# eth_ksz8567r_switch.net
KiCad netlist of a schematic drawn in Altium Designer
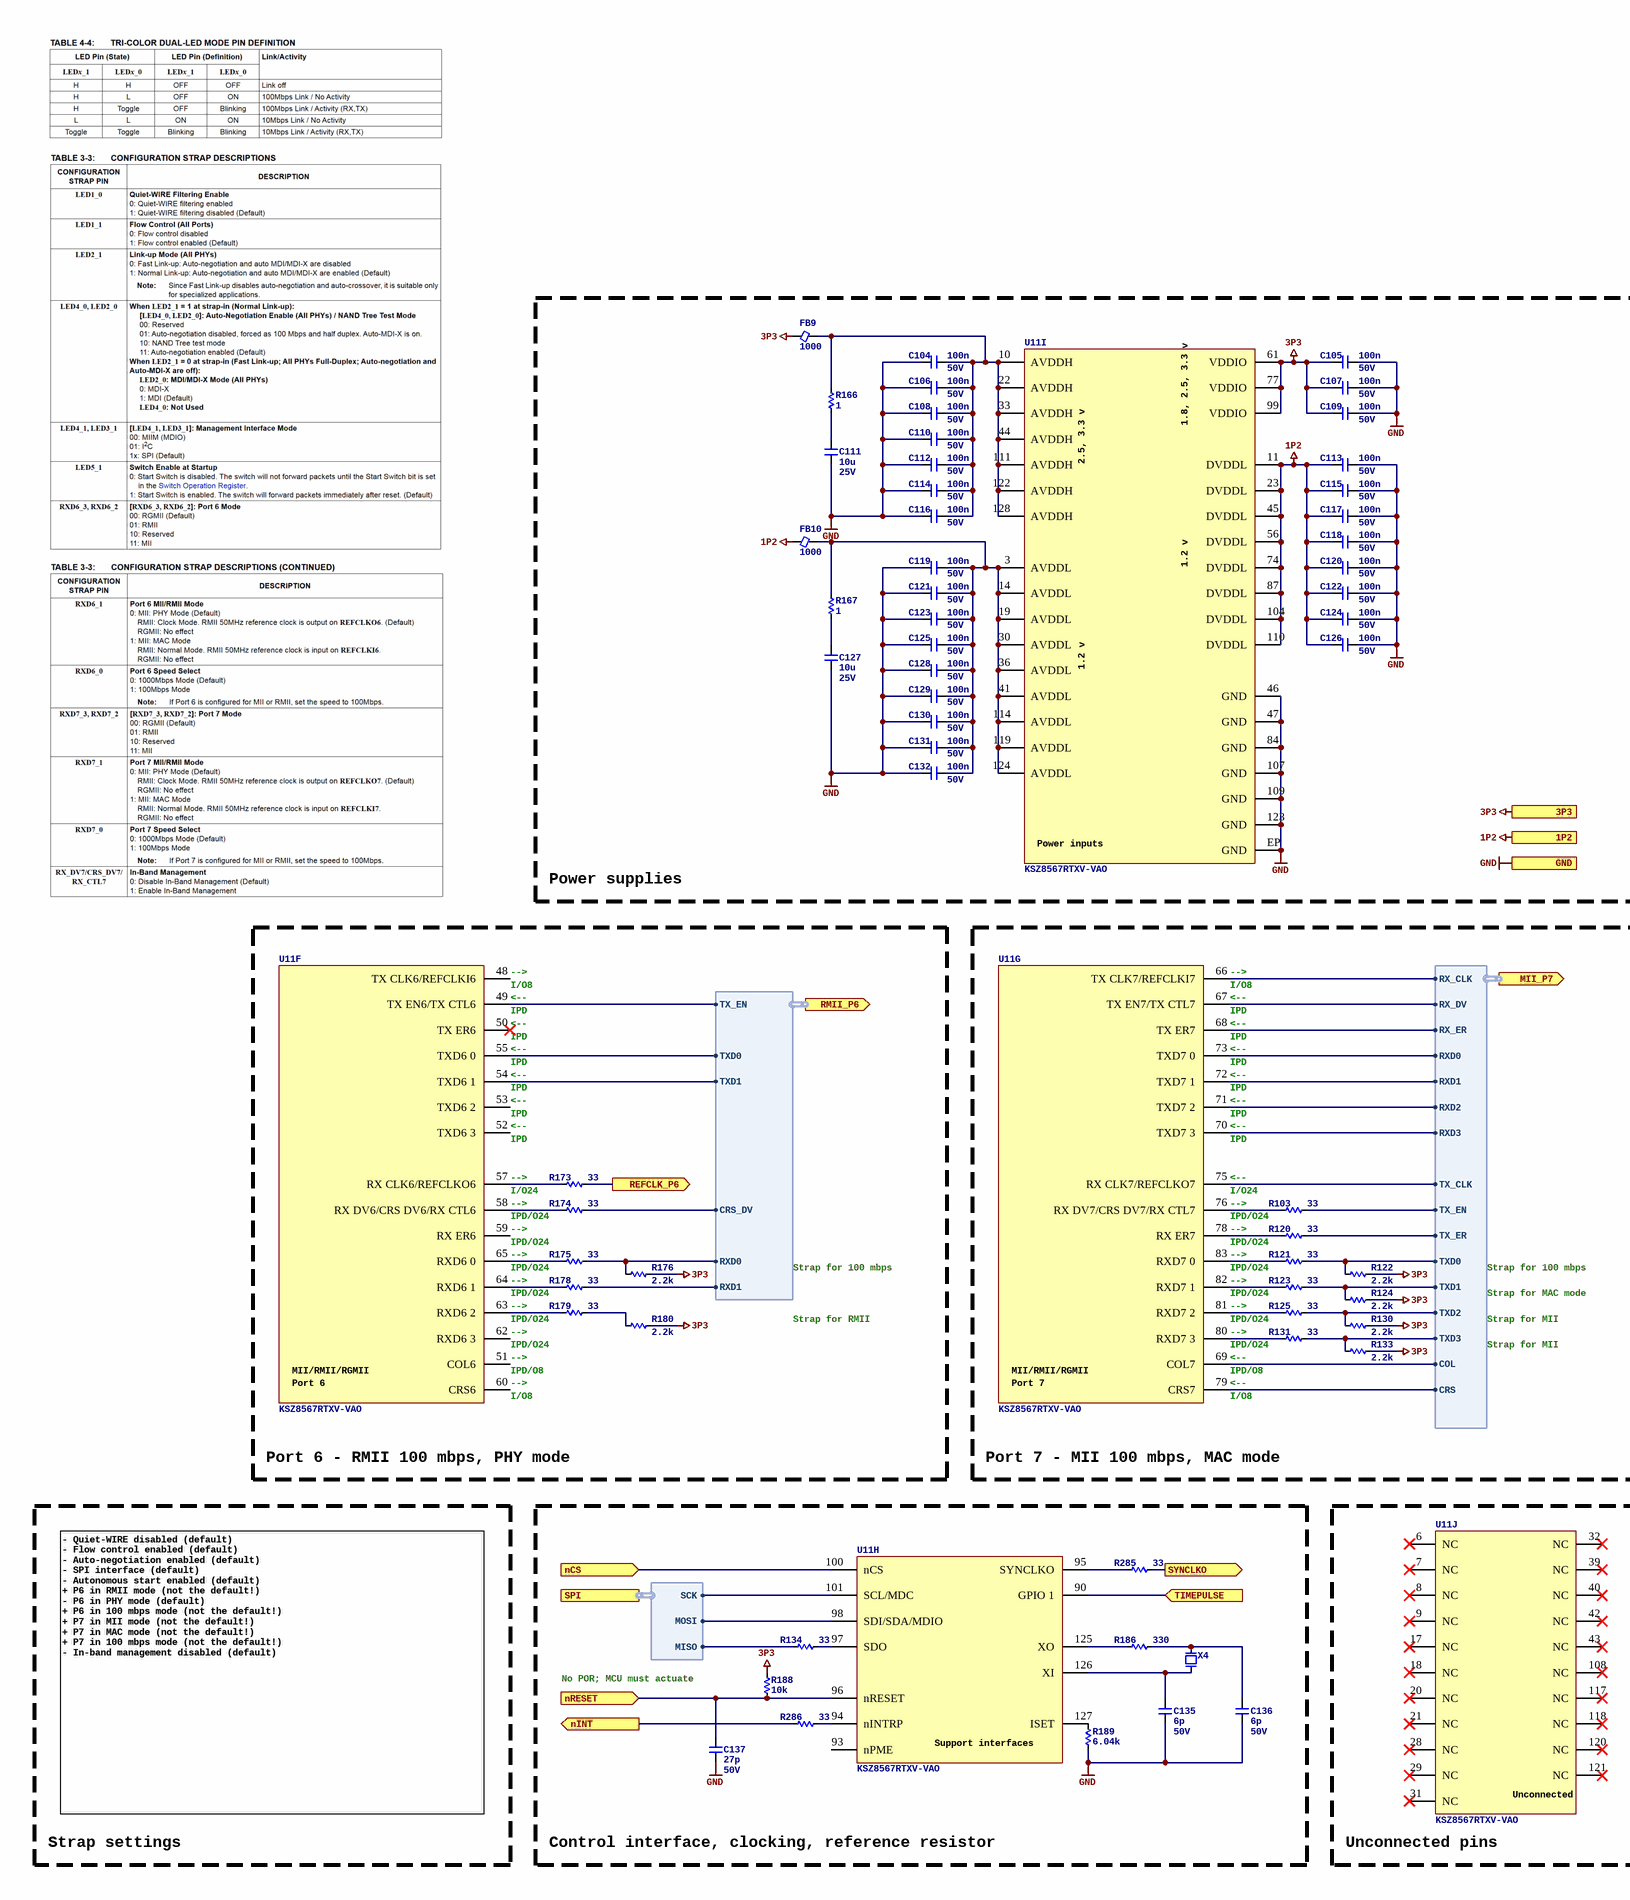
[diagram p0: eth_ksz8567r_switch.SchDoc, left]
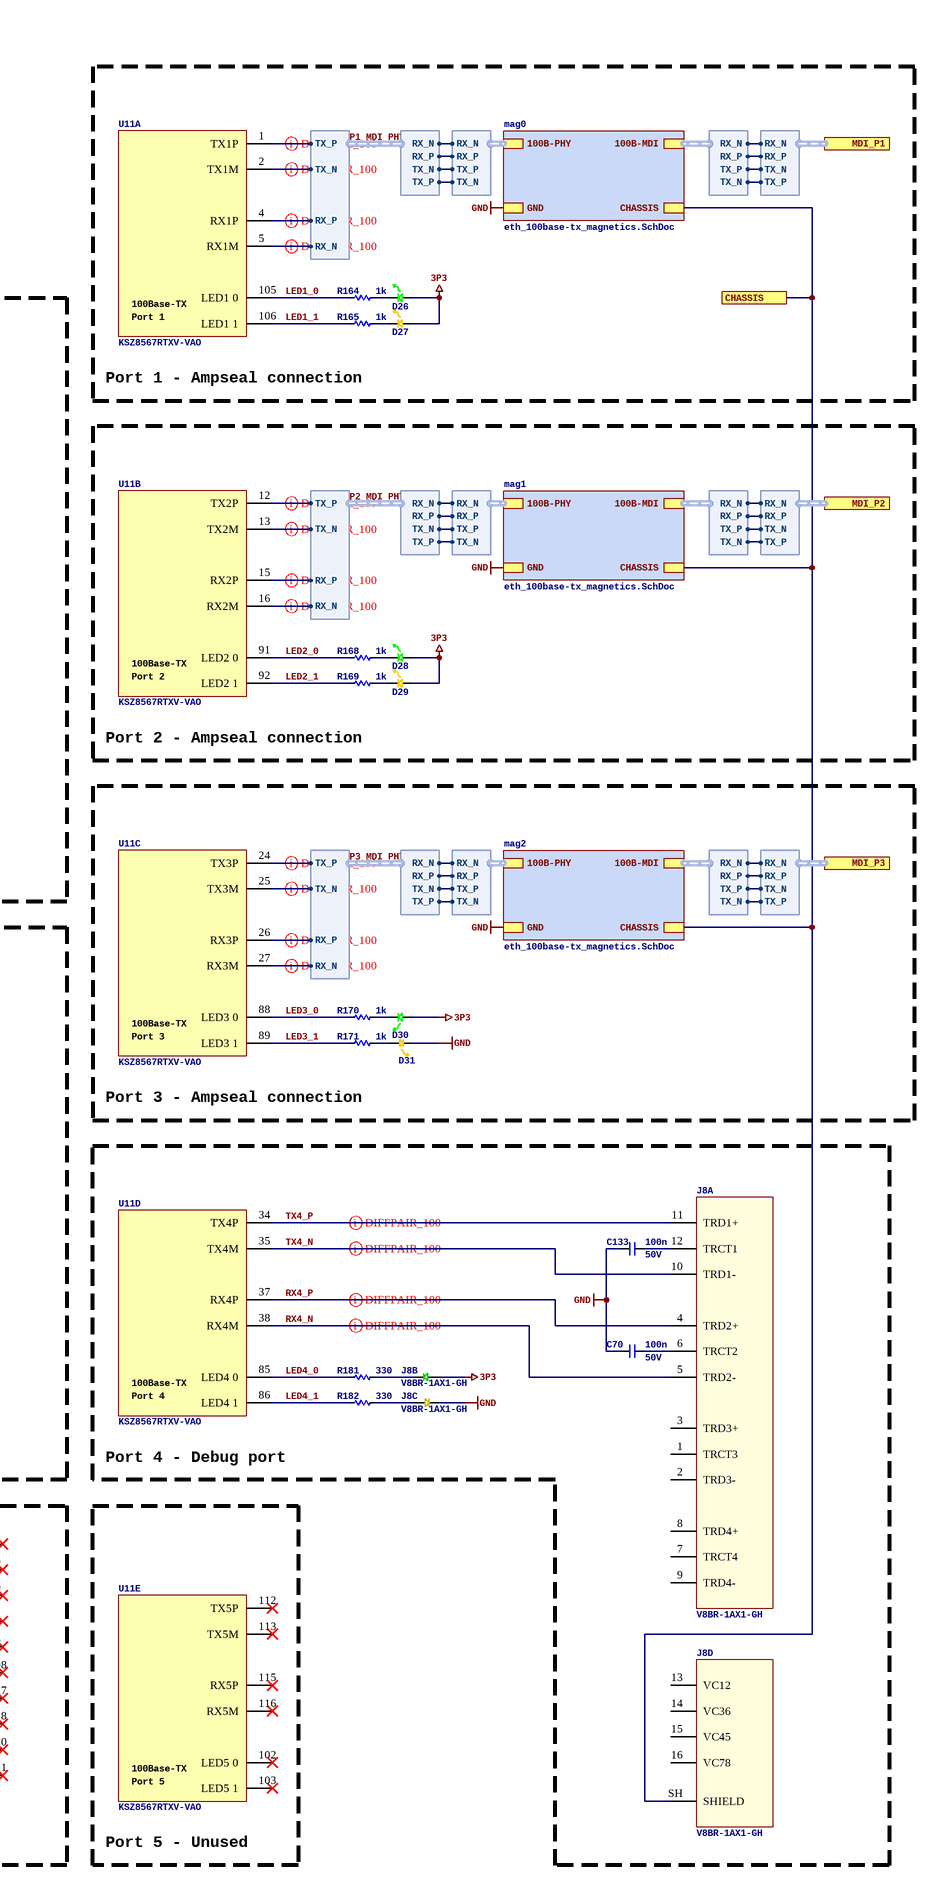
[diagram p1: eth_ksz8567r_switch.SchDoc, right]

(export (version "E")
  (design (tool "Eeschema 10.0.6"))
  (components
    (comp (ref "C70")
      (value "CL05B104KB54PNC")
      (footprint "C0402")
      (fields
        (field (name "CAPACITANCE") "100n")
        (field (name "MANUFACTURER") "Samsung Electro-Mechanics")
        (field (name "VOLTAGE RATING") "50V")
      )
      (libsource (lib "database") (part "__template_cap"))
    )
    (comp (ref "C104")
      (value "CL05B104KB54PNC")
      (footprint "C0402")
      (fields
        (field (name "CAPACITANCE") "100n")
        (field (name "MANUFACTURER") "Samsung Electro-Mechanics")
        (field (name "VOLTAGE RATING") "50V")
      )
      (libsource (lib "database") (part "__template_cap"))
    )
    (comp (ref "C105")
      (value "CL05B104KB54PNC")
      (footprint "C0402")
      (fields
        (field (name "CAPACITANCE") "100n")
        (field (name "MANUFACTURER") "Samsung Electro-Mechanics")
        (field (name "VOLTAGE RATING") "50V")
      )
      (libsource (lib "database") (part "__template_cap"))
    )
    (comp (ref "C106")
      (value "CL05B104KB54PNC")
      (footprint "C0402")
      (fields
        (field (name "CAPACITANCE") "100n")
        (field (name "MANUFACTURER") "Samsung Electro-Mechanics")
        (field (name "VOLTAGE RATING") "50V")
      )
      (libsource (lib "database") (part "__template_cap"))
    )
    (comp (ref "C107")
      (value "CL05B104KB54PNC")
      (footprint "C0402")
      (fields
        (field (name "CAPACITANCE") "100n")
        (field (name "MANUFACTURER") "Samsung Electro-Mechanics")
        (field (name "VOLTAGE RATING") "50V")
      )
      (libsource (lib "database") (part "__template_cap"))
    )
    (comp (ref "C108")
      (value "CL05B104KB54PNC")
      (footprint "C0402")
      (fields
        (field (name "CAPACITANCE") "100n")
        (field (name "MANUFACTURER") "Samsung Electro-Mechanics")
        (field (name "VOLTAGE RATING") "50V")
      )
      (libsource (lib "database") (part "__template_cap"))
    )
    (comp (ref "C109")
      (value "CL05B104KB54PNC")
      (footprint "C0402")
      (fields
        (field (name "CAPACITANCE") "100n")
        (field (name "MANUFACTURER") "Samsung Electro-Mechanics")
        (field (name "VOLTAGE RATING") "50V")
      )
      (libsource (lib "database") (part "__template_cap"))
    )
    (comp (ref "C110")
      (value "CL05B104KB54PNC")
      (footprint "C0402")
      (fields
        (field (name "CAPACITANCE") "100n")
        (field (name "MANUFACTURER") "Samsung Electro-Mechanics")
        (field (name "VOLTAGE RATING") "50V")
      )
      (libsource (lib "database") (part "__template_cap"))
    )
    (comp (ref "C111")
      (value "CL21B106KAYQNNE")
      (footprint "C0805")
      (fields
        (field (name "CAPACITANCE") "10u")
        (field (name "MANUFACTURER") "Samsung Electro-Mechanics")
        (field (name "VOLTAGE RATING") "25V")
      )
      (libsource (lib "database") (part "__template_cap"))
    )
    (comp (ref "C112")
      (value "CL05B104KB54PNC")
      (footprint "C0402")
      (fields
        (field (name "CAPACITANCE") "100n")
        (field (name "MANUFACTURER") "Samsung Electro-Mechanics")
        (field (name "VOLTAGE RATING") "50V")
      )
      (libsource (lib "database") (part "__template_cap"))
    )
    (comp (ref "C113")
      (value "CL05B104KB54PNC")
      (footprint "C0402")
      (fields
        (field (name "CAPACITANCE") "100n")
        (field (name "MANUFACTURER") "Samsung Electro-Mechanics")
        (field (name "VOLTAGE RATING") "50V")
      )
      (libsource (lib "database") (part "__template_cap"))
    )
    (comp (ref "C114")
      (value "CL05B104KB54PNC")
      (footprint "C0402")
      (fields
        (field (name "CAPACITANCE") "100n")
        (field (name "MANUFACTURER") "Samsung Electro-Mechanics")
        (field (name "VOLTAGE RATING") "50V")
      )
      (libsource (lib "database") (part "__template_cap"))
    )
    (comp (ref "C115")
      (value "CL05B104KB54PNC")
      (footprint "C0402")
      (fields
        (field (name "CAPACITANCE") "100n")
        (field (name "MANUFACTURER") "Samsung Electro-Mechanics")
        (field (name "VOLTAGE RATING") "50V")
      )
      (libsource (lib "database") (part "__template_cap"))
    )
    (comp (ref "C116")
      (value "CL05B104KB54PNC")
      (footprint "C0402")
      (fields
        (field (name "CAPACITANCE") "100n")
        (field (name "MANUFACTURER") "Samsung Electro-Mechanics")
        (field (name "VOLTAGE RATING") "50V")
      )
      (libsource (lib "database") (part "__template_cap"))
    )
    (comp (ref "C117")
      (value "CL05B104KB54PNC")
      (footprint "C0402")
      (fields
        (field (name "CAPACITANCE") "100n")
        (field (name "MANUFACTURER") "Samsung Electro-Mechanics")
        (field (name "VOLTAGE RATING") "50V")
      )
      (libsource (lib "database") (part "__template_cap"))
    )
    (comp (ref "C118")
      (value "CL05B104KB54PNC")
      (footprint "C0402")
      (fields
        (field (name "CAPACITANCE") "100n")
        (field (name "MANUFACTURER") "Samsung Electro-Mechanics")
        (field (name "VOLTAGE RATING") "50V")
      )
      (libsource (lib "database") (part "__template_cap"))
    )
    (comp (ref "C119")
      (value "CL05B104KB54PNC")
      (footprint "C0402")
      (fields
        (field (name "CAPACITANCE") "100n")
        (field (name "MANUFACTURER") "Samsung Electro-Mechanics")
        (field (name "VOLTAGE RATING") "50V")
      )
      (libsource (lib "database") (part "__template_cap"))
    )
    (comp (ref "C120")
      (value "CL05B104KB54PNC")
      (footprint "C0402")
      (fields
        (field (name "CAPACITANCE") "100n")
        (field (name "MANUFACTURER") "Samsung Electro-Mechanics")
        (field (name "VOLTAGE RATING") "50V")
      )
      (libsource (lib "database") (part "__template_cap"))
    )
    (comp (ref "C121")
      (value "CL05B104KB54PNC")
      (footprint "C0402")
      (fields
        (field (name "CAPACITANCE") "100n")
        (field (name "MANUFACTURER") "Samsung Electro-Mechanics")
        (field (name "VOLTAGE RATING") "50V")
      )
      (libsource (lib "database") (part "__template_cap"))
    )
    (comp (ref "C122")
      (value "CL05B104KB54PNC")
      (footprint "C0402")
      (fields
        (field (name "CAPACITANCE") "100n")
        (field (name "MANUFACTURER") "Samsung Electro-Mechanics")
        (field (name "VOLTAGE RATING") "50V")
      )
      (libsource (lib "database") (part "__template_cap"))
    )
    (comp (ref "C123")
      (value "CL05B104KB54PNC")
      (footprint "C0402")
      (fields
        (field (name "CAPACITANCE") "100n")
        (field (name "MANUFACTURER") "Samsung Electro-Mechanics")
        (field (name "VOLTAGE RATING") "50V")
      )
      (libsource (lib "database") (part "__template_cap"))
    )
    (comp (ref "C124")
      (value "CL05B104KB54PNC")
      (footprint "C0402")
      (fields
        (field (name "CAPACITANCE") "100n")
        (field (name "MANUFACTURER") "Samsung Electro-Mechanics")
        (field (name "VOLTAGE RATING") "50V")
      )
      (libsource (lib "database") (part "__template_cap"))
    )
    (comp (ref "C125")
      (value "CL05B104KB54PNC")
      (footprint "C0402")
      (fields
        (field (name "CAPACITANCE") "100n")
        (field (name "MANUFACTURER") "Samsung Electro-Mechanics")
        (field (name "VOLTAGE RATING") "50V")
      )
      (libsource (lib "database") (part "__template_cap"))
    )
    (comp (ref "C126")
      (value "CL05B104KB54PNC")
      (footprint "C0402")
      (fields
        (field (name "CAPACITANCE") "100n")
        (field (name "MANUFACTURER") "Samsung Electro-Mechanics")
        (field (name "VOLTAGE RATING") "50V")
      )
      (libsource (lib "database") (part "__template_cap"))
    )
    (comp (ref "C127")
      (value "CL21B106KAYQNNE")
      (footprint "C0805")
      (fields
        (field (name "CAPACITANCE") "10u")
        (field (name "MANUFACTURER") "Samsung Electro-Mechanics")
        (field (name "VOLTAGE RATING") "25V")
      )
      (libsource (lib "database") (part "__template_cap"))
    )
    (comp (ref "C128")
      (value "CL05B104KB54PNC")
      (footprint "C0402")
      (fields
        (field (name "CAPACITANCE") "100n")
        (field (name "MANUFACTURER") "Samsung Electro-Mechanics")
        (field (name "VOLTAGE RATING") "50V")
      )
      (libsource (lib "database") (part "__template_cap"))
    )
    (comp (ref "C129")
      (value "CL05B104KB54PNC")
      (footprint "C0402")
      (fields
        (field (name "CAPACITANCE") "100n")
        (field (name "MANUFACTURER") "Samsung Electro-Mechanics")
        (field (name "VOLTAGE RATING") "50V")
      )
      (libsource (lib "database") (part "__template_cap"))
    )
    (comp (ref "C130")
      (value "CL05B104KB54PNC")
      (footprint "C0402")
      (fields
        (field (name "CAPACITANCE") "100n")
        (field (name "MANUFACTURER") "Samsung Electro-Mechanics")
        (field (name "VOLTAGE RATING") "50V")
      )
      (libsource (lib "database") (part "__template_cap"))
    )
    (comp (ref "C131")
      (value "CL05B104KB54PNC")
      (footprint "C0402")
      (fields
        (field (name "CAPACITANCE") "100n")
        (field (name "MANUFACTURER") "Samsung Electro-Mechanics")
        (field (name "VOLTAGE RATING") "50V")
      )
      (libsource (lib "database") (part "__template_cap"))
    )
    (comp (ref "C132")
      (value "CL05B104KB54PNC")
      (footprint "C0402")
      (fields
        (field (name "CAPACITANCE") "100n")
        (field (name "MANUFACTURER") "Samsung Electro-Mechanics")
        (field (name "VOLTAGE RATING") "50V")
      )
      (libsource (lib "database") (part "__template_cap"))
    )
    (comp (ref "C133")
      (value "CL05B104KB54PNC")
      (footprint "C0402")
      (fields
        (field (name "CAPACITANCE") "100n")
        (field (name "MANUFACTURER") "Samsung Electro-Mechanics")
        (field (name "VOLTAGE RATING") "50V")
      )
      (libsource (lib "database") (part "__template_cap"))
    )
    (comp (ref "C135")
      (value "0402CG6R0C500NT")
      (footprint "C0402")
      (fields
        (field (name "CAPACITANCE") "6p")
        (field (name "MANUFACTURER") "FH(Guangdong Fenghua Advanced Tech)")
        (field (name "VOLTAGE RATING") "50V")
      )
      (libsource (lib "database") (part "__template_cap"))
    )
    (comp (ref "C136")
      (value "0402CG6R0C500NT")
      (footprint "C0402")
      (fields
        (field (name "CAPACITANCE") "6p")
        (field (name "MANUFACTURER") "FH(Guangdong Fenghua Advanced Tech)")
        (field (name "VOLTAGE RATING") "50V")
      )
      (libsource (lib "database") (part "__template_cap"))
    )
    (comp (ref "C137")
      (value "0402CG270J500NT")
      (footprint "C0402")
      (fields
        (field (name "CAPACITANCE") "27p")
        (field (name "MANUFACTURER") "FH(Guangdong Fenghua Advanced Tech)")
        (field (name "VOLTAGE RATING") "50V")
      )
      (libsource (lib "database") (part "__template_cap"))
    )
    (comp (ref "D26")
      (value "LTST-C190GKT")
      (footprint "LED_0603P_GREEN")
      (description "LED GREEN CLEAR 0603 SMD")
      (fields (field (name "MANUFACTURER") "Lite-On Inc"))
      (libsource (lib "SSCP") (part "LED_0603_GREEN_LTST-C190GKT"))
    )
    (comp (ref "D27")
      (value "LTST-C190AKT")
      (footprint "LED_0603P_AMBER")
      (description "LED AMBER CLEAR 0603 SMD")
      (fields (field (name "MANUFACTURER") "Lite-On Inc"))
      (libsource (lib "SSCP") (part "LED_0603_AMBER_LTST-C190AKT"))
    )
    (comp (ref "D28")
      (value "LTST-C190GKT")
      (footprint "LED_0603P_GREEN")
      (description "LED GREEN CLEAR 0603 SMD")
      (fields (field (name "MANUFACTURER") "Lite-On Inc"))
      (libsource (lib "SSCP") (part "LED_0603_GREEN_LTST-C190GKT"))
    )
    (comp (ref "D29")
      (value "LTST-C190AKT")
      (footprint "LED_0603P_AMBER")
      (description "LED AMBER CLEAR 0603 SMD")
      (fields (field (name "MANUFACTURER") "Lite-On Inc"))
      (libsource (lib "SSCP") (part "LED_0603_AMBER_LTST-C190AKT"))
    )
    (comp (ref "D30")
      (value "LTST-C190GKT")
      (footprint "LED_0603P_GREEN")
      (description "LED GREEN CLEAR 0603 SMD")
      (fields (field (name "MANUFACTURER") "Lite-On Inc"))
      (libsource (lib "") (part "LED_0603_GREEN_LTST-C190GKT_1"))
    )
    (comp (ref "D31")
      (value "LTST-C190AKT")
      (footprint "LED_0603P_AMBER")
      (description "LED AMBER CLEAR 0603 SMD")
      (fields (field (name "MANUFACTURER") "Lite-On Inc"))
      (libsource (lib "SSCP") (part "LED_0603_AMBER_LTST-C190AKT"))
    )
    (comp (ref "FB9")
      (value "HCB2012KF-102T10")
      (footprint "FB0805")
      (fields (field (name "MANUFACTURER") "TAI-TECH") (field (name "CURRENT RATING (MA)") "1000"))
      (libsource (lib "database") (part "__template_fb"))
    )
    (comp (ref "FB10")
      (value "HCB2012KF-102T10")
      (footprint "FB0805")
      (fields (field (name "MANUFACTURER") "TAI-TECH") (field (name "CURRENT RATING (MA)") "1000"))
      (libsource (lib "database") (part "__template_fb"))
    )
    (comp (ref "J8")
      (value "V8BR-1AX1-GH")
      (footprint "BELFUSE_V8BR-1AX1-GH")
      (description "Conn RJ-45 F 8 POS 1.02mm Solder ST Thru-Hole 20 Terminal 1 Port Tray")
      (fields (field (name "MANUFACTURER") "Bel"))
      (libsource (lib "SSCP") (part "CONN_BELFUSE_ETHERNET_V8BR-1AX1-GH"))
    )
    (comp (ref "R103")
      (value "33")
      (footprint "R0402")
      (fields
        (field (name "TOLERANCE") "1%")
        (field (name "MANUFACTURER PART NUMBER") "0402WGF330JTCE")
        (field (name "MANUFACTURER") "UNI-ROYAL(Uniroyal Elec)")
      )
      (libsource (lib "database") (part "__template_resistor"))
    )
    (comp (ref "R120")
      (value "33")
      (footprint "R0402")
      (fields
        (field (name "TOLERANCE") "1%")
        (field (name "MANUFACTURER PART NUMBER") "0402WGF330JTCE")
        (field (name "MANUFACTURER") "UNI-ROYAL(Uniroyal Elec)")
      )
      (libsource (lib "database") (part "__template_resistor"))
    )
    (comp (ref "R121")
      (value "33")
      (footprint "R0402")
      (fields
        (field (name "TOLERANCE") "1%")
        (field (name "MANUFACTURER PART NUMBER") "0402WGF330JTCE")
        (field (name "MANUFACTURER") "UNI-ROYAL(Uniroyal Elec)")
      )
      (libsource (lib "database") (part "__template_resistor"))
    )
    (comp (ref "R122")
      (value "2.2k")
      (footprint "R0402")
      (fields
        (field (name "TOLERANCE") "1%")
        (field (name "MANUFACTURER PART NUMBER") "0402WGF2201TCE")
        (field (name "MANUFACTURER") "UNI-ROYAL(Uniroyal Elec)")
      )
      (libsource (lib "database") (part "__template_resistor"))
    )
    (comp (ref "R123")
      (value "33")
      (footprint "R0402")
      (fields
        (field (name "TOLERANCE") "1%")
        (field (name "MANUFACTURER PART NUMBER") "0402WGF330JTCE")
        (field (name "MANUFACTURER") "UNI-ROYAL(Uniroyal Elec)")
      )
      (libsource (lib "database") (part "__template_resistor"))
    )
    (comp (ref "R124")
      (value "2.2k")
      (footprint "R0402")
      (fields
        (field (name "TOLERANCE") "1%")
        (field (name "MANUFACTURER PART NUMBER") "0402WGF2201TCE")
        (field (name "MANUFACTURER") "UNI-ROYAL(Uniroyal Elec)")
      )
      (libsource (lib "database") (part "__template_resistor"))
    )
    (comp (ref "R125")
      (value "33")
      (footprint "R0402")
      (fields
        (field (name "TOLERANCE") "1%")
        (field (name "MANUFACTURER PART NUMBER") "0402WGF330JTCE")
        (field (name "MANUFACTURER") "UNI-ROYAL(Uniroyal Elec)")
      )
      (libsource (lib "database") (part "__template_resistor"))
    )
    (comp (ref "R130")
      (value "2.2k")
      (footprint "R0402")
      (fields
        (field (name "TOLERANCE") "1%")
        (field (name "MANUFACTURER PART NUMBER") "0402WGF2201TCE")
        (field (name "MANUFACTURER") "UNI-ROYAL(Uniroyal Elec)")
      )
      (libsource (lib "database") (part "__template_resistor"))
    )
    (comp (ref "R131")
      (value "33")
      (footprint "R0402")
      (fields
        (field (name "TOLERANCE") "1%")
        (field (name "MANUFACTURER PART NUMBER") "0402WGF330JTCE")
        (field (name "MANUFACTURER") "UNI-ROYAL(Uniroyal Elec)")
      )
      (libsource (lib "database") (part "__template_resistor"))
    )
    (comp (ref "R133")
      (value "2.2k")
      (footprint "R0402")
      (fields
        (field (name "TOLERANCE") "1%")
        (field (name "MANUFACTURER PART NUMBER") "0402WGF2201TCE")
        (field (name "MANUFACTURER") "UNI-ROYAL(Uniroyal Elec)")
      )
      (libsource (lib "database") (part "__template_resistor"))
    )
    (comp (ref "R134")
      (value "33")
      (footprint "R0402")
      (fields
        (field (name "TOLERANCE") "1%")
        (field (name "MANUFACTURER PART NUMBER") "0402WGF330JTCE")
        (field (name "MANUFACTURER") "UNI-ROYAL(Uniroyal Elec)")
      )
      (libsource (lib "database") (part "__template_resistor"))
    )
    (comp (ref "R164")
      (value "1k")
      (footprint "R0402")
      (fields
        (field (name "TOLERANCE") "1%")
        (field (name "MANUFACTURER PART NUMBER") "0402WGF1001TCE")
        (field (name "MANUFACTURER") "UNI-ROYAL(Uniroyal Elec)")
      )
      (libsource (lib "database") (part "__template_resistor"))
    )
    (comp (ref "R165")
      (value "1k")
      (footprint "R0402")
      (fields
        (field (name "TOLERANCE") "1%")
        (field (name "MANUFACTURER PART NUMBER") "0402WGF1001TCE")
        (field (name "MANUFACTURER") "UNI-ROYAL(Uniroyal Elec)")
      )
      (libsource (lib "database") (part "__template_resistor"))
    )
    (comp (ref "R166")
      (value "1")
      (footprint "R0402")
      (fields
        (field (name "TOLERANCE") "1%")
        (field (name "MANUFACTURER PART NUMBER") "CRCW04021R00FKED")
        (field (name "MANUFACTURER") "Vishay Intertech")
      )
      (libsource (lib "database") (part "__template_resistor"))
    )
    (comp (ref "R167")
      (value "1")
      (footprint "R0402")
      (fields
        (field (name "TOLERANCE") "1%")
        (field (name "MANUFACTURER PART NUMBER") "CRCW04021R00FKED")
        (field (name "MANUFACTURER") "Vishay Intertech")
      )
      (libsource (lib "database") (part "__template_resistor"))
    )
    (comp (ref "R168")
      (value "1k")
      (footprint "R0402")
      (fields
        (field (name "TOLERANCE") "1%")
        (field (name "MANUFACTURER PART NUMBER") "0402WGF1001TCE")
        (field (name "MANUFACTURER") "UNI-ROYAL(Uniroyal Elec)")
      )
      (libsource (lib "database") (part "__template_resistor"))
    )
    (comp (ref "R169")
      (value "1k")
      (footprint "R0402")
      (fields
        (field (name "TOLERANCE") "1%")
        (field (name "MANUFACTURER PART NUMBER") "0402WGF1001TCE")
        (field (name "MANUFACTURER") "UNI-ROYAL(Uniroyal Elec)")
      )
      (libsource (lib "database") (part "__template_resistor"))
    )
    (comp (ref "R170")
      (value "1k")
      (footprint "R0402")
      (fields
        (field (name "TOLERANCE") "1%")
        (field (name "MANUFACTURER PART NUMBER") "0402WGF1001TCE")
        (field (name "MANUFACTURER") "UNI-ROYAL(Uniroyal Elec)")
      )
      (libsource (lib "database") (part "__template_resistor"))
    )
    (comp (ref "R171")
      (value "1k")
      (footprint "R0402")
      (fields
        (field (name "TOLERANCE") "1%")
        (field (name "MANUFACTURER PART NUMBER") "0402WGF1001TCE")
        (field (name "MANUFACTURER") "UNI-ROYAL(Uniroyal Elec)")
      )
      (libsource (lib "database") (part "__template_resistor"))
    )
    (comp (ref "R173")
      (value "33")
      (footprint "R0402")
      (fields
        (field (name "TOLERANCE") "1%")
        (field (name "MANUFACTURER PART NUMBER") "0402WGF330JTCE")
        (field (name "MANUFACTURER") "UNI-ROYAL(Uniroyal Elec)")
      )
      (libsource (lib "database") (part "__template_resistor"))
    )
    (comp (ref "R174")
      (value "33")
      (footprint "R0402")
      (fields
        (field (name "TOLERANCE") "1%")
        (field (name "MANUFACTURER PART NUMBER") "0402WGF330JTCE")
        (field (name "MANUFACTURER") "UNI-ROYAL(Uniroyal Elec)")
      )
      (libsource (lib "database") (part "__template_resistor"))
    )
    (comp (ref "R175")
      (value "33")
      (footprint "R0402")
      (fields
        (field (name "TOLERANCE") "1%")
        (field (name "MANUFACTURER PART NUMBER") "0402WGF330JTCE")
        (field (name "MANUFACTURER") "UNI-ROYAL(Uniroyal Elec)")
      )
      (libsource (lib "database") (part "__template_resistor"))
    )
    (comp (ref "R176")
      (value "2.2k")
      (footprint "R0402")
      (fields
        (field (name "TOLERANCE") "1%")
        (field (name "MANUFACTURER PART NUMBER") "0402WGF2201TCE")
        (field (name "MANUFACTURER") "UNI-ROYAL(Uniroyal Elec)")
      )
      (libsource (lib "database") (part "__template_resistor"))
    )
    (comp (ref "R178")
      (value "33")
      (footprint "R0402")
      (fields
        (field (name "TOLERANCE") "1%")
        (field (name "MANUFACTURER PART NUMBER") "0402WGF330JTCE")
        (field (name "MANUFACTURER") "UNI-ROYAL(Uniroyal Elec)")
      )
      (libsource (lib "database") (part "__template_resistor"))
    )
    (comp (ref "R179")
      (value "33")
      (footprint "R0402")
      (fields
        (field (name "TOLERANCE") "1%")
        (field (name "MANUFACTURER PART NUMBER") "0402WGF330JTCE")
        (field (name "MANUFACTURER") "UNI-ROYAL(Uniroyal Elec)")
      )
      (libsource (lib "database") (part "__template_resistor"))
    )
    (comp (ref "R180")
      (value "2.2k")
      (footprint "R0402")
      (fields
        (field (name "TOLERANCE") "1%")
        (field (name "MANUFACTURER PART NUMBER") "0402WGF2201TCE")
        (field (name "MANUFACTURER") "UNI-ROYAL(Uniroyal Elec)")
      )
      (libsource (lib "database") (part "__template_resistor"))
    )
    (comp (ref "R181")
      (value "330")
      (footprint "R0402")
      (fields
        (field (name "TOLERANCE") "1%")
        (field (name "MANUFACTURER PART NUMBER") "0402WGF3300TCE")
        (field (name "MANUFACTURER") "UNI-ROYAL(Uniroyal Elec)")
      )
      (libsource (lib "database") (part "__template_resistor"))
    )
    (comp (ref "R182")
      (value "330")
      (footprint "R0402")
      (fields
        (field (name "TOLERANCE") "1%")
        (field (name "MANUFACTURER PART NUMBER") "0402WGF3300TCE")
        (field (name "MANUFACTURER") "UNI-ROYAL(Uniroyal Elec)")
      )
      (libsource (lib "database") (part "__template_resistor"))
    )
    (comp (ref "R186")
      (value "330")
      (footprint "R0402")
      (fields
        (field (name "TOLERANCE") "1%")
        (field (name "MANUFACTURER PART NUMBER") "0402WGF3300TCE")
        (field (name "MANUFACTURER") "UNI-ROYAL(Uniroyal Elec)")
      )
      (libsource (lib "database") (part "__template_resistor"))
    )
    (comp (ref "R188")
      (value "10k")
      (footprint "R0402")
      (fields
        (field (name "TOLERANCE") "1%")
        (field (name "MANUFACTURER PART NUMBER") "0402WGF1002TCE")
        (field (name "MANUFACTURER") "UNI-ROYAL(Uniroyal Elec)")
      )
      (libsource (lib "database") (part "__template_resistor"))
    )
    (comp (ref "R189")
      (value "6.04k")
      (footprint "R0402")
      (fields
        (field (name "TOLERANCE") "1%")
        (field (name "MANUFACTURER PART NUMBER") "0402WGF6041TCE")
        (field (name "MANUFACTURER") "UNI-ROYAL(Uniroyal Elec)")
      )
      (libsource (lib "database") (part "__template_resistor"))
    )
    (comp (ref "R285")
      (value "33")
      (footprint "R0402")
      (fields
        (field (name "TOLERANCE") "1%")
        (field (name "MANUFACTURER PART NUMBER") "0402WGF330JTCE")
        (field (name "MANUFACTURER") "UNI-ROYAL(Uniroyal Elec)")
      )
      (libsource (lib "database") (part "__template_resistor"))
    )
    (comp (ref "R286")
      (value "33")
      (footprint "R0402")
      (fields
        (field (name "TOLERANCE") "1%")
        (field (name "MANUFACTURER PART NUMBER") "0402WGF330JTCE")
        (field (name "MANUFACTURER") "UNI-ROYAL(Uniroyal Elec)")
      )
      (libsource (lib "database") (part "__template_resistor"))
    )
    (comp (ref "U11")
      (value "KSZ8567RTXV-VAO")
      (footprint "MICROCHIP_C04-418B_128TQFP_14X14_10X10EP")
      (description "Automotive Ethernet Switch 7 Port 10Mbps/100Mbps 128-Pin TQFP EP Tray")
      (fields (field (name "MANUFACTURER") "Microchip"))
      (libsource (lib "SSCP") (part "ETH_SWITCH_7PORT_KSZ8567RTXV-VAO"))
    )
    (comp (ref "X4")
      (value "XRCGB25M000F3A00R0")
      (footprint "4_SMD_2.0X1.6MM")
      (description "CRYSTAL 25.000MHZ 6PF SMD")
      (fields (field (name "MANUFACTURER") "Murata"))
      (libsource (lib "SSCP") (part "XTAL_XRCGB25M000F3A00R0"))
    )
  )
  (nets
    (net (code "8") (name "/CHASSIS") (class "Default")
      (node (ref "J8") (pin "SH") (pinfunction "SHIELD_SH") (pintype "passive"))
    )
    (net (code "9") (name "/COL") (class "Default")
      (node (ref "U11") (pin "69") (pinfunction "COL7_69") (pintype "passive"))
    )
    (net (code "10") (name "/CRS") (class "Default")
      (node (ref "U11") (pin "79") (pinfunction "CRS7_79") (pintype "passive"))
    )
    (net (code "11") (name "/CRS_DV") (class "Default") (node (ref "R174") (pin "1") (pintype "passive")))
    (net (code "12") (name "/LED1_0") (class "Default")
      (node (ref "R164") (pin "2") (pintype "passive"))
      (node (ref "U11") (pin "105") (pinfunction "LED1_0_105") (pintype "passive"))
    )
    (net (code "13") (name "/LED1_1") (class "Default")
      (node (ref "R165") (pin "2") (pintype "passive"))
      (node (ref "U11") (pin "106") (pinfunction "LED1_1_106") (pintype "passive"))
    )
    (net (code "14") (name "/LED2_0") (class "Default")
      (node (ref "R168") (pin "2") (pintype "passive"))
      (node (ref "U11") (pin "91") (pinfunction "LED2_0_91") (pintype "passive"))
    )
    (net (code "15") (name "/LED2_1") (class "Default")
      (node (ref "R169") (pin "2") (pintype "passive"))
      (node (ref "U11") (pin "92") (pinfunction "LED2_1_92") (pintype "passive"))
    )
    (net (code "16") (name "/LED3_0") (class "Default")
      (node (ref "R170") (pin "2") (pintype "passive"))
      (node (ref "U11") (pin "88") (pinfunction "LED3_0_88") (pintype "passive"))
    )
    (net (code "17") (name "/LED3_1") (class "Default")
      (node (ref "R171") (pin "2") (pintype "passive"))
      (node (ref "U11") (pin "89") (pinfunction "LED3_1_89") (pintype "passive"))
    )
    (net (code "18") (name "/LED4_0") (class "Default")
      (node (ref "R181") (pin "1") (pintype "passive"))
      (node (ref "U11") (pin "85") (pinfunction "LED4_0_85") (pintype "passive"))
    )
    (net (code "19") (name "/LED4_1") (class "Default")
      (node (ref "R182") (pin "1") (pintype "passive"))
      (node (ref "U11") (pin "86") (pinfunction "LED4_1_86") (pintype "passive"))
    )
    (net (code "20") (name "/MISO") (class "Default") (node (ref "R134") (pin "2") (pintype "passive")))
    (net (code "21") (name "/MOSI") (class "Default")
      (node (ref "U11") (pin "98") (pinfunction "SDI/SDA/MDIO_98") (pintype "passive"))
    )
    (net (code "25") (name "/REFCLK_P6") (class "Default") (node (ref "R173") (pin "1") (pintype "passive")))
    (net (code "26") (name "/RX4_N") (class "Default")
      (node (ref "J8") (pin "5") (pinfunction "TRD2-_5") (pintype "passive"))
      (node (ref "U11") (pin "38") (pinfunction "RX4M_38") (pintype "passive"))
    )
    (net (code "27") (name "/RX4_P") (class "Default")
      (node (ref "J8") (pin "4") (pinfunction "TRD2+_4") (pintype "passive"))
      (node (ref "U11") (pin "37") (pinfunction "RX4P_37") (pintype "passive"))
    )
    (net (code "28") (name "/RXD2") (class "Default")
      (node (ref "U11") (pin "71") (pinfunction "TXD7_2_71") (pintype "passive"))
    )
    (net (code "29") (name "/RXD3") (class "Default")
      (node (ref "U11") (pin "70") (pinfunction "TXD7_3_70") (pintype "passive"))
    )
    (net (code "30") (name "/RX_CLK") (class "Default")
      (node (ref "U11") (pin "66") (pinfunction "TX_CLK7/REFCLKI7_66") (pintype "passive"))
    )
    (net (code "31") (name "/RX_DV") (class "Default")
      (node (ref "U11") (pin "67") (pinfunction "TX_EN7/TX_CTL7_67") (pintype "passive"))
    )
    (net (code "32") (name "/RX_ER") (class "Default")
      (node (ref "U11") (pin "68") (pinfunction "TX_ER7_68") (pintype "passive"))
    )
    (net (code "33") (name "/SCK") (class "Default")
      (node (ref "U11") (pin "101") (pinfunction "SCL/MDC_101") (pintype "passive"))
    )
    (net (code "34") (name "/SYNCLKO") (class "Default") (node (ref "R285") (pin "1") (pintype "passive")))
    (net (code "35") (name "/TIMEPULSE") (class "Default")
      (node (ref "U11") (pin "90") (pinfunction "GPIO_1_90") (pintype "passive"))
    )
    (net (code "36") (name "/TX4_N") (class "Default")
      (node (ref "J8") (pin "10") (pinfunction "TRD1-_10") (pintype "passive"))
      (node (ref "U11") (pin "35") (pinfunction "TX4M_35") (pintype "passive"))
    )
    (net (code "37") (name "/TX4_P") (class "Default")
      (node (ref "J8") (pin "11") (pinfunction "TRD1+_11") (pintype "passive"))
      (node (ref "U11") (pin "34") (pinfunction "TX4P_34") (pintype "passive"))
    )
    (net (code "38") (name "/TXD2") (class "Default")
      (node (ref "R125") (pin "1") (pintype "passive"))
      (node (ref "R130") (pin "2") (pintype "passive"))
    )
    (net (code "39") (name "/TXD3") (class "Default")
      (node (ref "R131") (pin "1") (pintype "passive"))
      (node (ref "R133") (pin "2") (pintype "passive"))
    )
    (net (code "40") (name "/TX_CLK") (class "Default")
      (node (ref "U11") (pin "75") (pinfunction "RX_CLK7/REFCLKO7_75") (pintype "passive"))
    )
    (net (code "41") (name "/TX_ER") (class "Default") (node (ref "R120") (pin "1") (pintype "passive")))
    (net (code "42") (name "/nCS") (class "Default")
      (node (ref "U11") (pin "100") (pinfunction "nCS_100") (pintype "passive"))
    )
    (net (code "43") (name "/nINT") (class "Default") (node (ref "R286") (pin "2") (pintype "passive")))
    (net (code "44") (name "/nRESET") (class "Default")
      (node (ref "C137") (pin "1") (pintype "passive"))
      (node (ref "R188") (pin "2") (pintype "passive"))
      (node (ref "U11") (pin "96") (pinfunction "nRESET_96") (pintype "passive"))
    )
    (net (code "49") (name "1P2") (class "Default")
      (node (ref "C113") (pin "1") (pintype "passive"))
      (node (ref "C115") (pin "1") (pintype "passive"))
      (node (ref "C117") (pin "1") (pintype "passive"))
      (node (ref "C118") (pin "1") (pintype "passive"))
      (node (ref "C120") (pin "1") (pintype "passive"))
      (node (ref "C122") (pin "1") (pintype "passive"))
      (node (ref "C124") (pin "1") (pintype "passive"))
      (node (ref "C126") (pin "1") (pintype "passive"))
      (node (ref "FB10") (pin "1") (pintype "passive"))
      (node (ref "U11") (pin "104") (pinfunction "DVDDL_104") (pintype "passive"))
      (node (ref "U11") (pin "11") (pinfunction "DVDDL_11") (pintype "passive"))
      (node (ref "U11") (pin "110") (pinfunction "DVDDL_110") (pintype "passive"))
      (node (ref "U11") (pin "23") (pinfunction "DVDDL_23") (pintype "passive"))
      (node (ref "U11") (pin "45") (pinfunction "DVDDL_45") (pintype "passive"))
      (node (ref "U11") (pin "56") (pinfunction "DVDDL_56") (pintype "passive"))
      (node (ref "U11") (pin "74") (pinfunction "DVDDL_74") (pintype "passive"))
      (node (ref "U11") (pin "87") (pinfunction "DVDDL_87") (pintype "passive"))
    )
    (net (code "50") (name "3P3") (class "Default")
      (node (ref "C105") (pin "1") (pintype "passive"))
      (node (ref "C107") (pin "1") (pintype "passive"))
      (node (ref "C109") (pin "1") (pintype "passive"))
      (node (ref "D26") (pin "2") (pintype "passive"))
      (node (ref "D27") (pin "2") (pintype "passive"))
      (node (ref "D28") (pin "2") (pintype "passive"))
      (node (ref "D29") (pin "2") (pintype "passive"))
      (node (ref "D30") (pin "2") (pintype "passive"))
      (node (ref "FB9") (pin "1") (pintype "passive"))
      (node (ref "J8") (pin "20") (pintype "passive"))
      (node (ref "R122") (pin "1") (pintype "passive"))
      (node (ref "R124") (pin "1") (pintype "passive"))
      (node (ref "R130") (pin "1") (pintype "passive"))
      (node (ref "R133") (pin "1") (pintype "passive"))
      (node (ref "R176") (pin "1") (pintype "passive"))
      (node (ref "R180") (pin "1") (pintype "passive"))
      (node (ref "R188") (pin "1") (pintype "passive"))
      (node (ref "U11") (pin "61") (pinfunction "VDDIO_61") (pintype "passive"))
      (node (ref "U11") (pin "77") (pinfunction "VDDIO_77") (pintype "passive"))
      (node (ref "U11") (pin "99") (pinfunction "VDDIO_99") (pintype "passive"))
    )
    (net (code "51") (name "GND") (class "Default")
      (node (ref "C104") (pin "2") (pintype "passive"))
      (node (ref "C105") (pin "2") (pintype "passive"))
      (node (ref "C106") (pin "2") (pintype "passive"))
      (node (ref "C107") (pin "2") (pintype "passive"))
      (node (ref "C108") (pin "2") (pintype "passive"))
      (node (ref "C109") (pin "2") (pintype "passive"))
      (node (ref "C110") (pin "2") (pintype "passive"))
      (node (ref "C111") (pin "2") (pintype "passive"))
      (node (ref "C112") (pin "2") (pintype "passive"))
      (node (ref "C113") (pin "2") (pintype "passive"))
      (node (ref "C114") (pin "2") (pintype "passive"))
      (node (ref "C115") (pin "2") (pintype "passive"))
      (node (ref "C116") (pin "2") (pintype "passive"))
      (node (ref "C117") (pin "2") (pintype "passive"))
      (node (ref "C118") (pin "2") (pintype "passive"))
      (node (ref "C119") (pin "2") (pintype "passive"))
      (node (ref "C120") (pin "2") (pintype "passive"))
      (node (ref "C121") (pin "2") (pintype "passive"))
      (node (ref "C122") (pin "2") (pintype "passive"))
      (node (ref "C123") (pin "2") (pintype "passive"))
      (node (ref "C124") (pin "2") (pintype "passive"))
      (node (ref "C125") (pin "2") (pintype "passive"))
      (node (ref "C126") (pin "2") (pintype "passive"))
      (node (ref "C127") (pin "2") (pintype "passive"))
      (node (ref "C128") (pin "2") (pintype "passive"))
      (node (ref "C129") (pin "2") (pintype "passive"))
      (node (ref "C130") (pin "2") (pintype "passive"))
      (node (ref "C131") (pin "2") (pintype "passive"))
      (node (ref "C132") (pin "2") (pintype "passive"))
      (node (ref "C133") (pin "2") (pintype "passive"))
      (node (ref "C135") (pin "2") (pintype "passive"))
      (node (ref "C136") (pin "2") (pintype "passive"))
      (node (ref "C137") (pin "2") (pintype "passive"))
      (node (ref "C70") (pin "2") (pintype "passive"))
      (node (ref "D31") (pin "1") (pintype "passive"))
      (node (ref "J8") (pin "17") (pintype "passive"))
      (node (ref "R189") (pin "2") (pintype "passive"))
      (node (ref "U11") (pin "107") (pinfunction "GND_107") (pintype "passive"))
      (node (ref "U11") (pin "109") (pinfunction "GND_109") (pintype "passive"))
      (node (ref "U11") (pin "123") (pinfunction "GND_123") (pintype "passive"))
      (node (ref "U11") (pin "46") (pinfunction "GND_46") (pintype "passive"))
      (node (ref "U11") (pin "47") (pinfunction "GND_47") (pintype "passive"))
      (node (ref "U11") (pin "84") (pinfunction "GND_84") (pintype "passive"))
      (node (ref "U11") (pin "EP") (pinfunction "GND_EP") (pintype "passive"))
    )
    (net (code "52") (name "Net-(C104-Pad1)") (class "Default")
      (node (ref "C104") (pin "1") (pintype "passive"))
      (node (ref "C106") (pin "1") (pintype "passive"))
      (node (ref "C108") (pin "1") (pintype "passive"))
      (node (ref "C110") (pin "1") (pintype "passive"))
      (node (ref "C112") (pin "1") (pintype "passive"))
      (node (ref "C114") (pin "1") (pintype "passive"))
      (node (ref "C116") (pin "1") (pintype "passive"))
      (node (ref "FB9") (pin "2") (pintype "passive"))
      (node (ref "R166") (pin "2") (pintype "passive"))
      (node (ref "U11") (pin "10") (pinfunction "AVDDH_10") (pintype "passive"))
      (node (ref "U11") (pin "111") (pinfunction "AVDDH_111") (pintype "passive"))
      (node (ref "U11") (pin "122") (pinfunction "AVDDH_122") (pintype "passive"))
      (node (ref "U11") (pin "128") (pinfunction "AVDDH_128") (pintype "passive"))
      (node (ref "U11") (pin "22") (pinfunction "AVDDH_22") (pintype "passive"))
      (node (ref "U11") (pin "33") (pinfunction "AVDDH_33") (pintype "passive"))
      (node (ref "U11") (pin "44") (pinfunction "AVDDH_44") (pintype "passive"))
    )
    (net (code "53") (name "Net-(C111-Pad1)") (class "Default")
      (node (ref "C111") (pin "1") (pintype "passive"))
      (node (ref "R166") (pin "1") (pintype "passive"))
    )
    (net (code "54") (name "Net-(C119-Pad1)") (class "Default")
      (node (ref "C119") (pin "1") (pintype "passive"))
      (node (ref "C121") (pin "1") (pintype "passive"))
      (node (ref "C123") (pin "1") (pintype "passive"))
      (node (ref "C125") (pin "1") (pintype "passive"))
      (node (ref "C128") (pin "1") (pintype "passive"))
      (node (ref "C129") (pin "1") (pintype "passive"))
      (node (ref "C130") (pin "1") (pintype "passive"))
      (node (ref "C131") (pin "1") (pintype "passive"))
      (node (ref "C132") (pin "1") (pintype "passive"))
      (node (ref "FB10") (pin "2") (pintype "passive"))
      (node (ref "R167") (pin "2") (pintype "passive"))
      (node (ref "U11") (pin "114") (pinfunction "AVDDL_114") (pintype "passive"))
      (node (ref "U11") (pin "119") (pinfunction "AVDDL_119") (pintype "passive"))
      (node (ref "U11") (pin "124") (pinfunction "AVDDL_124") (pintype "passive"))
      (node (ref "U11") (pin "14") (pinfunction "AVDDL_14") (pintype "passive"))
      (node (ref "U11") (pin "19") (pinfunction "AVDDL_19") (pintype "passive"))
      (node (ref "U11") (pin "3") (pinfunction "AVDDL_3") (pintype "passive"))
      (node (ref "U11") (pin "30") (pinfunction "AVDDL_30") (pintype "passive"))
      (node (ref "U11") (pin "36") (pinfunction "AVDDL_36") (pintype "passive"))
      (node (ref "U11") (pin "41") (pinfunction "AVDDL_41") (pintype "passive"))
    )
    (net (code "55") (name "Net-(C127-Pad1)") (class "Default")
      (node (ref "C127") (pin "1") (pintype "passive"))
      (node (ref "R167") (pin "1") (pintype "passive"))
    )
    (net (code "56") (name "Net-(C136-Pad1)") (class "Default")
      (node (ref "C136") (pin "1") (pintype "passive"))
      (node (ref "R186") (pin "2") (pintype "passive"))
      (node (ref "X4") (pin "3") (pinfunction "3_3") (pintype "passive"))
    )
    (net (code "57") (name "Net-(D26-Pad1)") (class "Default")
      (node (ref "D26") (pin "1") (pintype "passive"))
      (node (ref "R164") (pin "1") (pintype "passive"))
    )
    (net (code "58") (name "Net-(D27-Pad1)") (class "Default")
      (node (ref "D27") (pin "1") (pintype "passive"))
      (node (ref "R165") (pin "1") (pintype "passive"))
    )
    (net (code "59") (name "Net-(D28-Pad1)") (class "Default")
      (node (ref "D28") (pin "1") (pintype "passive"))
      (node (ref "R168") (pin "1") (pintype "passive"))
    )
    (net (code "60") (name "Net-(D29-Pad1)") (class "Default")
      (node (ref "D29") (pin "1") (pintype "passive"))
      (node (ref "R169") (pin "1") (pintype "passive"))
    )
    (net (code "61") (name "Net-(D30-Pad1)") (class "Default")
      (node (ref "D30") (pin "1") (pintype "passive"))
      (node (ref "R170") (pin "1") (pintype "passive"))
    )
    (net (code "62") (name "Net-(D31-Pad2)") (class "Default")
      (node (ref "D31") (pin "2") (pintype "passive"))
      (node (ref "R171") (pin "1") (pintype "passive"))
    )
    (net (code "63") (name "Net-(J8-Pad18)") (class "Default")
      (node (ref "J8") (pin "18") (pintype "passive"))
      (node (ref "R182") (pin "2") (pintype "passive"))
    )
    (net (code "64") (name "Net-(J8-Pad19)") (class "Default")
      (node (ref "J8") (pin "19") (pintype "passive"))
      (node (ref "R181") (pin "2") (pintype "passive"))
    )
    (net (code "65") (name "Net-(J8A-TRCT1)") (class "Default")
      (node (ref "C133") (pin "1") (pintype "passive"))
      (node (ref "J8") (pin "12") (pinfunction "TRCT1_12") (pintype "passive"))
    )
    (net (code "66") (name "Net-(J8A-TRCT2)") (class "Default")
      (node (ref "C70") (pin "1") (pintype "passive"))
      (node (ref "J8") (pin "6") (pinfunction "TRCT2_6") (pintype "passive"))
    )
    (net (code "67") (name "Net-(R121-Pad1)") (class "Default")
      (node (ref "R121") (pin "1") (pintype "passive"))
      (node (ref "R122") (pin "2") (pintype "passive"))
    )
    (net (code "68") (name "Net-(R123-Pad1)") (class "Default")
      (node (ref "R123") (pin "1") (pintype "passive"))
      (node (ref "R124") (pin "2") (pintype "passive"))
    )
    (net (code "69") (name "Net-(R175-Pad1)") (class "Default")
      (node (ref "R175") (pin "1") (pintype "passive"))
      (node (ref "R176") (pin "2") (pintype "passive"))
    )
    (net (code "70") (name "Net-(R179-Pad1)") (class "Default")
      (node (ref "R179") (pin "1") (pintype "passive"))
      (node (ref "R180") (pin "2") (pintype "passive"))
    )
    (net (code "71") (name "Net-(U11F-RXD6_0)") (class "Default")
      (node (ref "R175") (pin "2") (pintype "passive"))
      (node (ref "U11") (pin "65") (pinfunction "RXD6_0_65") (pintype "passive"))
    )
    (net (code "72") (name "Net-(U11F-RXD6_1)") (class "Default")
      (node (ref "R178") (pin "2") (pintype "passive"))
      (node (ref "U11") (pin "64") (pinfunction "RXD6_1_64") (pintype "passive"))
    )
    (net (code "73") (name "Net-(U11F-RXD6_2)") (class "Default")
      (node (ref "R179") (pin "2") (pintype "passive"))
      (node (ref "U11") (pin "63") (pinfunction "RXD6_2_63") (pintype "passive"))
    )
    (net (code "74") (name "Net-(U11F-RX_CLK6{slash}REFCLKO6)") (class "Default")
      (node (ref "R173") (pin "2") (pintype "passive"))
      (node (ref "U11") (pin "57") (pinfunction "RX_CLK6/REFCLKO6_57") (pintype "passive"))
    )
    (net (code "75") (name "Net-(U11F-RX_DV6{slash}CRS_DV6{slash}RX_CTL6)") (class "Default")
      (node (ref "R174") (pin "2") (pintype "passive"))
      (node (ref "U11") (pin "58") (pinfunction "RX_DV6/CRS_DV6/RX_CTL6_58") (pintype "passive"))
    )
    (net (code "76") (name "Net-(U11G-RXD7_0)") (class "Default")
      (node (ref "R121") (pin "2") (pintype "passive"))
      (node (ref "U11") (pin "83") (pinfunction "RXD7_0_83") (pintype "passive"))
    )
    (net (code "77") (name "Net-(U11G-RXD7_1)") (class "Default")
      (node (ref "R123") (pin "2") (pintype "passive"))
      (node (ref "U11") (pin "82") (pinfunction "RXD7_1_82") (pintype "passive"))
    )
    (net (code "78") (name "Net-(U11G-RXD7_2)") (class "Default")
      (node (ref "R125") (pin "2") (pintype "passive"))
      (node (ref "U11") (pin "81") (pinfunction "RXD7_2_81") (pintype "passive"))
    )
    (net (code "79") (name "Net-(U11G-RXD7_3)") (class "Default")
      (node (ref "R131") (pin "2") (pintype "passive"))
      (node (ref "U11") (pin "80") (pinfunction "RXD7_3_80") (pintype "passive"))
    )
    (net (code "80") (name "Net-(U11G-RX_DV7{slash}CRS_DV7{slash}RX_CTL7)") (class "Default")
      (node (ref "R103") (pin "2") (pintype "passive"))
      (node (ref "U11") (pin "76") (pinfunction "RX_DV7/CRS_DV7/RX_CTL7_76") (pintype "passive"))
    )
    (net (code "81") (name "Net-(U11G-RX_ER7)") (class "Default")
      (node (ref "R120") (pin "2") (pintype "passive"))
      (node (ref "U11") (pin "78") (pinfunction "RX_ER7_78") (pintype "passive"))
    )
    (net (code "82") (name "Net-(U11H-ISET)") (class "Default")
      (node (ref "R189") (pin "1") (pintype "passive"))
      (node (ref "U11") (pin "127") (pinfunction "ISET_127") (pintype "passive"))
    )
    (net (code "83") (name "Net-(U11H-SDO)") (class "Default")
      (node (ref "R134") (pin "1") (pintype "passive"))
      (node (ref "U11") (pin "97") (pinfunction "SDO_97") (pintype "passive"))
    )
    (net (code "84") (name "Net-(U11H-SYNCLKO)") (class "Default")
      (node (ref "R285") (pin "2") (pintype "passive"))
      (node (ref "U11") (pin "95") (pinfunction "SYNCLKO_95") (pintype "passive"))
    )
    (net (code "85") (name "Net-(U11H-XI)") (class "Default")
      (node (ref "C135") (pin "1") (pintype "passive"))
      (node (ref "U11") (pin "126") (pinfunction "XI_126") (pintype "passive"))
      (node (ref "X4") (pin "1") (pinfunction "1_1") (pintype "passive"))
    )
    (net (code "86") (name "Net-(U11H-XO)") (class "Default")
      (node (ref "R186") (pin "1") (pintype "passive"))
      (node (ref "U11") (pin "125") (pinfunction "XO_125") (pintype "passive"))
    )
    (net (code "87") (name "Net-(U11H-nINTRP)") (class "Default")
      (node (ref "R286") (pin "1") (pintype "passive"))
      (node (ref "U11") (pin "94") (pinfunction "nINTRP_94") (pintype "passive"))
    )
    (net (code "88") (name "unconnected-(J8A-TRCT3-Pad1)") (class "Default")
      (node (ref "J8") (pin "1") (pinfunction "TRCT3_1") (pintype "passive"))
    )
    (net (code "89") (name "unconnected-(J8A-TRCT4-Pad7)") (class "Default")
      (node (ref "J8") (pin "7") (pinfunction "TRCT4_7") (pintype "passive"))
    )
    (net (code "90") (name "unconnected-(J8A-TRD3+-Pad3)") (class "Default")
      (node (ref "J8") (pin "3") (pinfunction "TRD3+_3") (pintype "passive"))
    )
    (net (code "91") (name "unconnected-(J8A-TRD3--Pad2)") (class "Default")
      (node (ref "J8") (pin "2") (pinfunction "TRD3-_2") (pintype "passive"))
    )
    (net (code "92") (name "unconnected-(J8A-TRD4+-Pad8)") (class "Default")
      (node (ref "J8") (pin "8") (pinfunction "TRD4+_8") (pintype "passive"))
    )
    (net (code "93") (name "unconnected-(J8A-TRD4--Pad9)") (class "Default")
      (node (ref "J8") (pin "9") (pinfunction "TRD4-_9") (pintype "passive"))
    )
    (net (code "94") (name "unconnected-(J8D-VC12-Pad13)") (class "Default")
      (node (ref "J8") (pin "13") (pinfunction "VC12_13") (pintype "passive"))
    )
    (net (code "95") (name "unconnected-(J8D-VC36-Pad14)") (class "Default")
      (node (ref "J8") (pin "14") (pinfunction "VC36_14") (pintype "passive"))
    )
    (net (code "96") (name "unconnected-(J8D-VC45-Pad15)") (class "Default")
      (node (ref "J8") (pin "15") (pinfunction "VC45_15") (pintype "passive"))
    )
    (net (code "97") (name "unconnected-(J8D-VC78-Pad16)") (class "Default")
      (node (ref "J8") (pin "16") (pinfunction "VC78_16") (pintype "passive"))
    )
    (net (code "98") (name "unconnected-(R103-Pad1)") (class "Default")
      (node (ref "R103") (pin "1") (pintype "passive"))
    )
    (net (code "99") (name "unconnected-(R178-Pad1)") (class "Default")
      (node (ref "R178") (pin "1") (pintype "passive"))
    )
    (net (code "100") (name "unconnected-(U11A-RX1M-Pad5)") (class "Default")
      (node (ref "U11") (pin "5") (pinfunction "RX1M_5") (pintype "passive"))
    )
    (net (code "101") (name "unconnected-(U11A-RX1P-Pad4)") (class "Default")
      (node (ref "U11") (pin "4") (pinfunction "RX1P_4") (pintype "passive"))
    )
    (net (code "102") (name "unconnected-(U11A-TX1M-Pad2)") (class "Default")
      (node (ref "U11") (pin "2") (pinfunction "TX1M_2") (pintype "passive"))
    )
    (net (code "103") (name "unconnected-(U11A-TX1P-Pad1)") (class "Default")
      (node (ref "U11") (pin "1") (pinfunction "TX1P_1") (pintype "passive"))
    )
    (net (code "104") (name "unconnected-(U11B-RX2M-Pad16)") (class "Default")
      (node (ref "U11") (pin "16") (pinfunction "RX2M_16") (pintype "passive"))
    )
    (net (code "105") (name "unconnected-(U11B-RX2P-Pad15)") (class "Default")
      (node (ref "U11") (pin "15") (pinfunction "RX2P_15") (pintype "passive"))
    )
    (net (code "106") (name "unconnected-(U11B-TX2M-Pad13)") (class "Default")
      (node (ref "U11") (pin "13") (pinfunction "TX2M_13") (pintype "passive"))
    )
    (net (code "107") (name "unconnected-(U11B-TX2P-Pad12)") (class "Default")
      (node (ref "U11") (pin "12") (pinfunction "TX2P_12") (pintype "passive"))
    )
    (net (code "108") (name "unconnected-(U11C-RX3M-Pad27)") (class "Default")
      (node (ref "U11") (pin "27") (pinfunction "RX3M_27") (pintype "passive"))
    )
    (net (code "109") (name "unconnected-(U11C-RX3P-Pad26)") (class "Default")
      (node (ref "U11") (pin "26") (pinfunction "RX3P_26") (pintype "passive"))
    )
    (net (code "110") (name "unconnected-(U11C-TX3M-Pad25)") (class "Default")
      (node (ref "U11") (pin "25") (pinfunction "TX3M_25") (pintype "passive"))
    )
    (net (code "111") (name "unconnected-(U11C-TX3P-Pad24)") (class "Default")
      (node (ref "U11") (pin "24") (pinfunction "TX3P_24") (pintype "passive"))
    )
    (net (code "112") (name "unconnected-(U11E-LED5_0-Pad102)") (class "Default")
      (node (ref "U11") (pin "102") (pinfunction "LED5_0_102") (pintype "passive+no_connect"))
    )
    (net (code "113") (name "unconnected-(U11E-LED5_1-Pad103)") (class "Default")
      (node (ref "U11") (pin "103") (pinfunction "LED5_1_103") (pintype "passive+no_connect"))
    )
    (net (code "114") (name "unconnected-(U11E-RX5M-Pad116)") (class "Default")
      (node (ref "U11") (pin "116") (pinfunction "RX5M_116") (pintype "passive+no_connect"))
    )
    (net (code "115") (name "unconnected-(U11E-RX5P-Pad115)") (class "Default")
      (node (ref "U11") (pin "115") (pinfunction "RX5P_115") (pintype "passive+no_connect"))
    )
    (net (code "116") (name "unconnected-(U11E-TX5M-Pad113)") (class "Default")
      (node (ref "U11") (pin "113") (pinfunction "TX5M_113") (pintype "passive+no_connect"))
    )
    (net (code "117") (name "unconnected-(U11E-TX5P-Pad112)") (class "Default")
      (node (ref "U11") (pin "112") (pinfunction "TX5P_112") (pintype "passive+no_connect"))
    )
    (net (code "118") (name "unconnected-(U11F-COL6-Pad51)") (class "Default")
      (node (ref "U11") (pin "51") (pinfunction "COL6_51") (pintype "passive"))
    )
    (net (code "119") (name "unconnected-(U11F-CRS6-Pad60)") (class "Default")
      (node (ref "U11") (pin "60") (pinfunction "CRS6_60") (pintype "passive"))
    )
    (net (code "120") (name "unconnected-(U11F-RXD6_3-Pad62)") (class "Default")
      (node (ref "U11") (pin "62") (pinfunction "RXD6_3_62") (pintype "passive"))
    )
    (net (code "121") (name "unconnected-(U11F-RX_ER6-Pad59)") (class "Default")
      (node (ref "U11") (pin "59") (pinfunction "RX_ER6_59") (pintype "passive"))
    )
    (net (code "122") (name "unconnected-(U11F-TXD6_0-Pad55)") (class "Default")
      (node (ref "U11") (pin "55") (pinfunction "TXD6_0_55") (pintype "passive"))
    )
    (net (code "123") (name "unconnected-(U11F-TXD6_1-Pad54)") (class "Default")
      (node (ref "U11") (pin "54") (pinfunction "TXD6_1_54") (pintype "passive"))
    )
    (net (code "124") (name "unconnected-(U11F-TXD6_2-Pad53)") (class "Default")
      (node (ref "U11") (pin "53") (pinfunction "TXD6_2_53") (pintype "passive"))
    )
    (net (code "125") (name "unconnected-(U11F-TXD6_3-Pad52)") (class "Default")
      (node (ref "U11") (pin "52") (pinfunction "TXD6_3_52") (pintype "passive"))
    )
    (net (code "126") (name "unconnected-(U11F-TX_CLK6{slash}REFCLKI6-Pad48)") (class "Default")
      (node (ref "U11") (pin "48") (pinfunction "TX_CLK6/REFCLKI6_48") (pintype "passive"))
    )
    (net (code "127") (name "unconnected-(U11F-TX_EN6{slash}TX_CTL6-Pad49)") (class "Default")
      (node (ref "U11") (pin "49") (pinfunction "TX_EN6/TX_CTL6_49") (pintype "passive"))
    )
    (net (code "128") (name "unconnected-(U11F-TX_ER6-Pad50)") (class "Default")
      (node (ref "U11") (pin "50") (pinfunction "TX_ER6_50") (pintype "passive+no_connect"))
    )
    (net (code "129") (name "unconnected-(U11G-TXD7_0-Pad73)") (class "Default")
      (node (ref "U11") (pin "73") (pinfunction "TXD7_0_73") (pintype "passive"))
    )
    (net (code "130") (name "unconnected-(U11G-TXD7_1-Pad72)") (class "Default")
      (node (ref "U11") (pin "72") (pinfunction "TXD7_1_72") (pintype "passive"))
    )
    (net (code "131") (name "unconnected-(U11H-nPME-Pad93)") (class "Default")
      (node (ref "U11") (pin "93") (pinfunction "nPME_93") (pintype "passive"))
    )
    (net (code "132") (name "unconnected-(U11J-NC-Pad6)") (class "Default")
      (node (ref "U11") (pin "6") (pinfunction "NC_6") (pintype "passive+no_connect"))
    )
    (net (code "133") (name "unconnected-(U11J-NC-Pad7)") (class "Default")
      (node (ref "U11") (pin "7") (pinfunction "NC_7") (pintype "passive+no_connect"))
    )
    (net (code "134") (name "unconnected-(U11J-NC-Pad8)") (class "Default")
      (node (ref "U11") (pin "8") (pinfunction "NC_8") (pintype "passive+no_connect"))
    )
    (net (code "135") (name "unconnected-(U11J-NC-Pad9)") (class "Default")
      (node (ref "U11") (pin "9") (pinfunction "NC_9") (pintype "passive+no_connect"))
    )
    (net (code "136") (name "unconnected-(U11J-NC-Pad17)") (class "Default")
      (node (ref "U11") (pin "17") (pinfunction "NC_17") (pintype "passive+no_connect"))
    )
    (net (code "137") (name "unconnected-(U11J-NC-Pad18)") (class "Default")
      (node (ref "U11") (pin "18") (pinfunction "NC_18") (pintype "passive+no_connect"))
    )
    (net (code "138") (name "unconnected-(U11J-NC-Pad20)") (class "Default")
      (node (ref "U11") (pin "20") (pinfunction "NC_20") (pintype "passive+no_connect"))
    )
    (net (code "139") (name "unconnected-(U11J-NC-Pad21)") (class "Default")
      (node (ref "U11") (pin "21") (pinfunction "NC_21") (pintype "passive+no_connect"))
    )
    (net (code "140") (name "unconnected-(U11J-NC-Pad28)") (class "Default")
      (node (ref "U11") (pin "28") (pinfunction "NC_28") (pintype "passive+no_connect"))
    )
    (net (code "141") (name "unconnected-(U11J-NC-Pad29)") (class "Default")
      (node (ref "U11") (pin "29") (pinfunction "NC_29") (pintype "passive+no_connect"))
    )
    (net (code "142") (name "unconnected-(U11J-NC-Pad31)") (class "Default")
      (node (ref "U11") (pin "31") (pinfunction "NC_31") (pintype "passive+no_connect"))
    )
    (net (code "143") (name "unconnected-(U11J-NC-Pad32)") (class "Default")
      (node (ref "U11") (pin "32") (pinfunction "NC_32") (pintype "passive+no_connect"))
    )
    (net (code "144") (name "unconnected-(U11J-NC-Pad39)") (class "Default")
      (node (ref "U11") (pin "39") (pinfunction "NC_39") (pintype "passive+no_connect"))
    )
    (net (code "145") (name "unconnected-(U11J-NC-Pad40)") (class "Default")
      (node (ref "U11") (pin "40") (pinfunction "NC_40") (pintype "passive+no_connect"))
    )
    (net (code "146") (name "unconnected-(U11J-NC-Pad42)") (class "Default")
      (node (ref "U11") (pin "42") (pinfunction "NC_42") (pintype "passive+no_connect"))
    )
    (net (code "147") (name "unconnected-(U11J-NC-Pad43)") (class "Default")
      (node (ref "U11") (pin "43") (pinfunction "NC_43") (pintype "passive+no_connect"))
    )
    (net (code "148") (name "unconnected-(U11J-NC-Pad108)") (class "Default")
      (node (ref "U11") (pin "108") (pinfunction "NC_108") (pintype "passive+no_connect"))
    )
    (net (code "149") (name "unconnected-(U11J-NC-Pad117)") (class "Default")
      (node (ref "U11") (pin "117") (pinfunction "NC_117") (pintype "passive+no_connect"))
    )
    (net (code "150") (name "unconnected-(U11J-NC-Pad118)") (class "Default")
      (node (ref "U11") (pin "118") (pinfunction "NC_118") (pintype "passive+no_connect"))
    )
    (net (code "151") (name "unconnected-(U11J-NC-Pad120)") (class "Default")
      (node (ref "U11") (pin "120") (pinfunction "NC_120") (pintype "passive+no_connect"))
    )
    (net (code "152") (name "unconnected-(U11J-NC-Pad121)") (class "Default")
      (node (ref "U11") (pin "121") (pinfunction "NC_121") (pintype "passive+no_connect"))
    )
  )
)
